# main.net
KiCad netlist of a schematic drawn in EAGLE
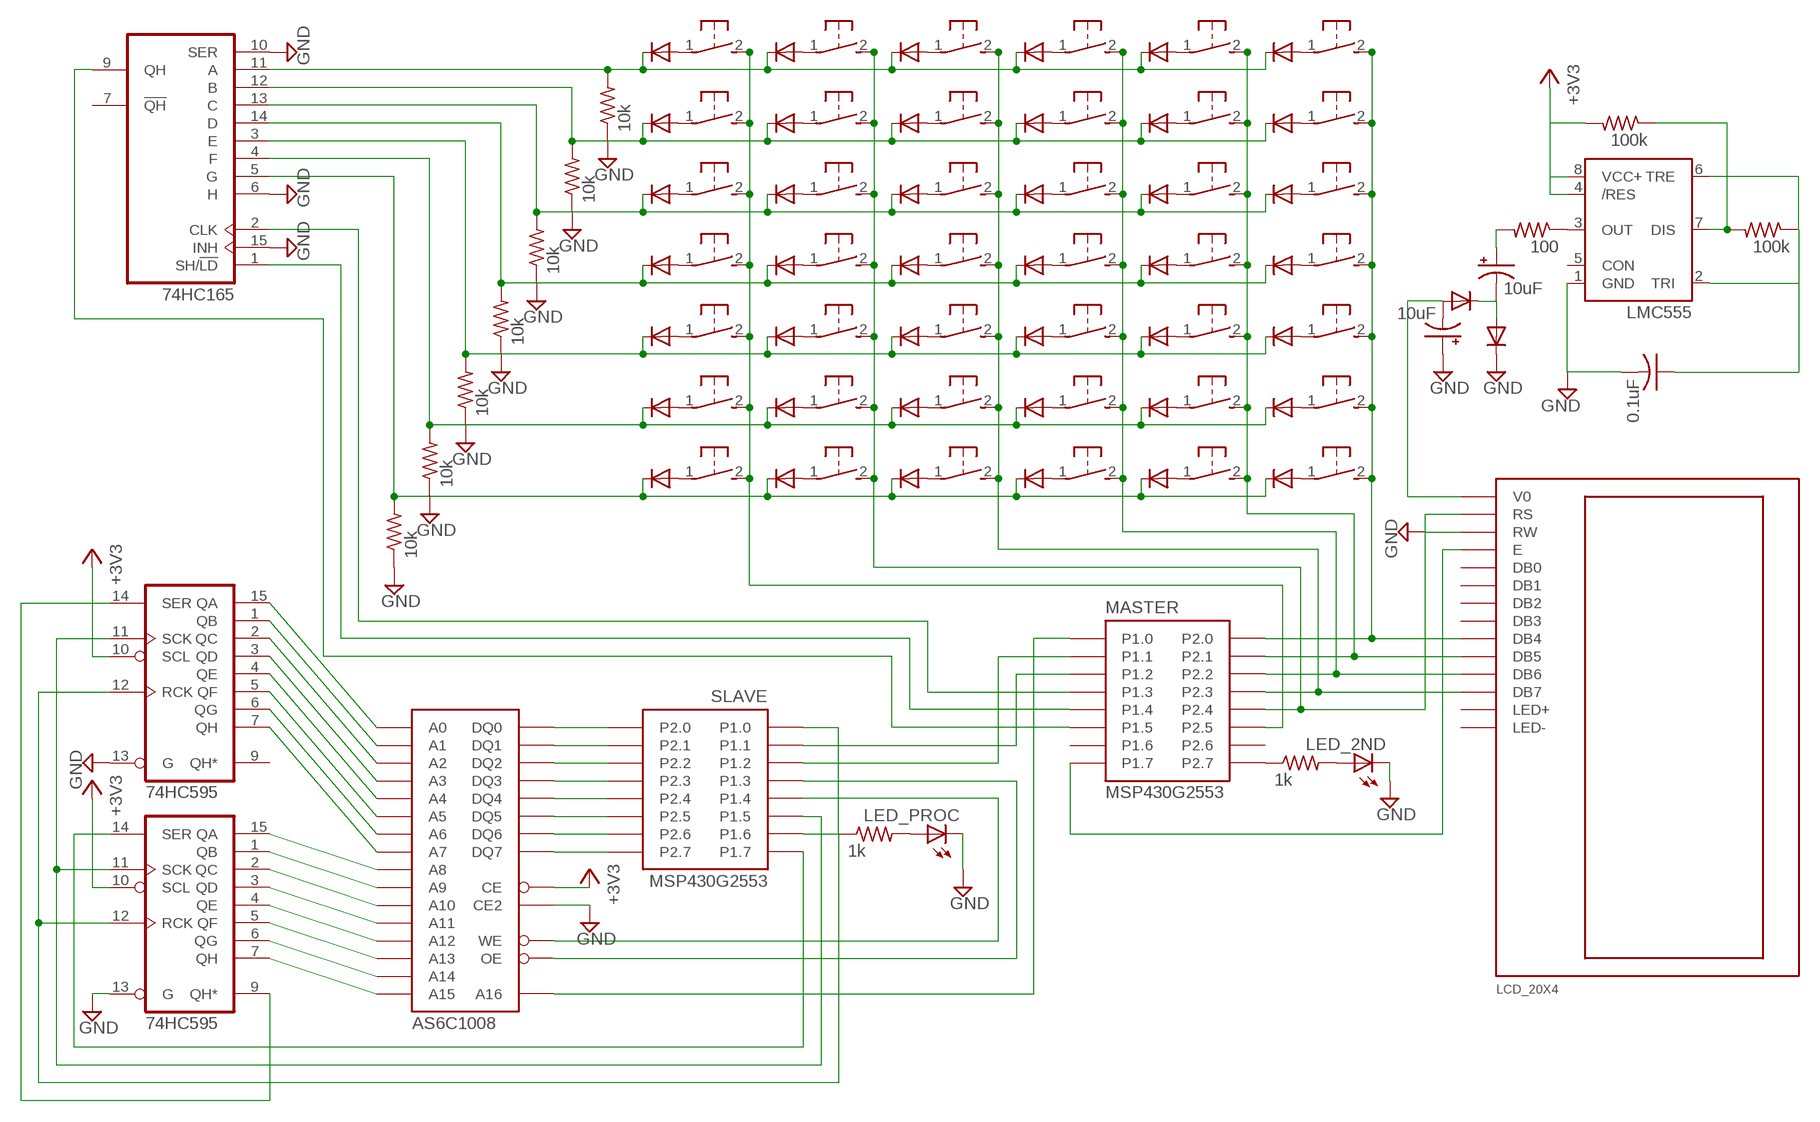
[diagram p0: schematic, sheet 1]

(export (version "E")
  (design (tool "Eeschema 10.0.6"))
  (components
    (comp (ref "C2")
      (value "0.1uF")
      (footprint "eagle-import:C025-024X044")
      (libsource (lib "eagle-import") (part "C-US025-024X044"))
    )
    (comp (ref "C4")
      (value "10uF")
      (footprint "eagle-import:085CS_1AW")
      (libsource (lib "eagle-import") (part "CPOL-US085CS-1AW"))
    )
    (comp (ref "C5")
      (value "10uF")
      (footprint "eagle-import:085CS_1AW")
      (libsource (lib "eagle-import") (part "CPOL-US085CS-1AW"))
    )
    (comp (ref "D1")
      (value "1N4148DO35-7")
      (footprint "eagle-import:DO35-7")
      (libsource (lib "eagle-import") (part "1N4148DO35-7"))
    )
    (comp (ref "D2")
      (value "1N4148DO35-7")
      (footprint "eagle-import:DO35-7")
      (libsource (lib "eagle-import") (part "1N4148DO35-7"))
    )
    (comp (ref "D3")
      (value "1N4148DO35-7")
      (footprint "eagle-import:DO35-7")
      (libsource (lib "eagle-import") (part "1N4148DO35-7"))
    )
    (comp (ref "D4")
      (value "1N4148DO35-7")
      (footprint "eagle-import:DO35-7")
      (libsource (lib "eagle-import") (part "1N4148DO35-7"))
    )
    (comp (ref "D5")
      (value "1N4148DO35-7")
      (footprint "eagle-import:DO35-7")
      (libsource (lib "eagle-import") (part "1N4148DO35-7"))
    )
    (comp (ref "D6")
      (value "1N4148DO35-7")
      (footprint "eagle-import:DO35-7")
      (libsource (lib "eagle-import") (part "1N4148DO35-7"))
    )
    (comp (ref "D7")
      (value "1N4148DO35-7")
      (footprint "eagle-import:DO35-7")
      (libsource (lib "eagle-import") (part "1N4148DO35-7"))
    )
    (comp (ref "D8")
      (value "1N4148DO35-7")
      (footprint "eagle-import:DO35-7")
      (libsource (lib "eagle-import") (part "1N4148DO35-7"))
    )
    (comp (ref "D9")
      (value "1N4148DO35-7")
      (footprint "eagle-import:DO35-7")
      (libsource (lib "eagle-import") (part "1N4148DO35-7"))
    )
    (comp (ref "D10")
      (value "1N4148DO35-7")
      (footprint "eagle-import:DO35-7")
      (libsource (lib "eagle-import") (part "1N4148DO35-7"))
    )
    (comp (ref "D11")
      (value "1N4148DO35-7")
      (footprint "eagle-import:DO35-7")
      (libsource (lib "eagle-import") (part "1N4148DO35-7"))
    )
    (comp (ref "D12")
      (value "1N4148DO35-7")
      (footprint "eagle-import:DO35-7")
      (libsource (lib "eagle-import") (part "1N4148DO35-7"))
    )
    (comp (ref "D13")
      (value "1N4148DO35-7")
      (footprint "eagle-import:DO35-7")
      (libsource (lib "eagle-import") (part "1N4148DO35-7"))
    )
    (comp (ref "D14")
      (value "1N4148DO35-7")
      (footprint "eagle-import:DO35-7")
      (libsource (lib "eagle-import") (part "1N4148DO35-7"))
    )
    (comp (ref "D15")
      (value "1N4148DO35-7")
      (footprint "eagle-import:DO35-7")
      (libsource (lib "eagle-import") (part "1N4148DO35-7"))
    )
    (comp (ref "D16")
      (value "1N4148DO35-7")
      (footprint "eagle-import:DO35-7")
      (libsource (lib "eagle-import") (part "1N4148DO35-7"))
    )
    (comp (ref "D17")
      (value "1N4148DO35-7")
      (footprint "eagle-import:DO35-7")
      (libsource (lib "eagle-import") (part "1N4148DO35-7"))
    )
    (comp (ref "D18")
      (value "1N4148DO35-7")
      (footprint "eagle-import:DO35-7")
      (libsource (lib "eagle-import") (part "1N4148DO35-7"))
    )
    (comp (ref "D19")
      (value "1N4148DO35-7")
      (footprint "eagle-import:DO35-7")
      (libsource (lib "eagle-import") (part "1N4148DO35-7"))
    )
    (comp (ref "D20")
      (value "1N4148DO35-7")
      (footprint "eagle-import:DO35-7")
      (libsource (lib "eagle-import") (part "1N4148DO35-7"))
    )
    (comp (ref "D21")
      (value "1N4148DO35-7")
      (footprint "eagle-import:DO35-7")
      (libsource (lib "eagle-import") (part "1N4148DO35-7"))
    )
    (comp (ref "D22")
      (value "1N4148DO35-7")
      (footprint "eagle-import:DO35-7")
      (libsource (lib "eagle-import") (part "1N4148DO35-7"))
    )
    (comp (ref "D23")
      (value "1N4148DO35-7")
      (footprint "eagle-import:DO35-7")
      (libsource (lib "eagle-import") (part "1N4148DO35-7"))
    )
    (comp (ref "D24")
      (value "1N4148DO35-7")
      (footprint "eagle-import:DO35-7")
      (libsource (lib "eagle-import") (part "1N4148DO35-7"))
    )
    (comp (ref "D25")
      (value "1N4148DO35-7")
      (footprint "eagle-import:DO35-7")
      (libsource (lib "eagle-import") (part "1N4148DO35-7"))
    )
    (comp (ref "D26")
      (value "1N4148DO35-7")
      (footprint "eagle-import:DO35-7")
      (libsource (lib "eagle-import") (part "1N4148DO35-7"))
    )
    (comp (ref "D27")
      (value "1N4148DO35-7")
      (footprint "eagle-import:DO35-7")
      (libsource (lib "eagle-import") (part "1N4148DO35-7"))
    )
    (comp (ref "D28")
      (value "1N4148DO35-7")
      (footprint "eagle-import:DO35-7")
      (libsource (lib "eagle-import") (part "1N4148DO35-7"))
    )
    (comp (ref "D29")
      (value "1N4148DO35-7")
      (footprint "eagle-import:DO35-7")
      (libsource (lib "eagle-import") (part "1N4148DO35-7"))
    )
    (comp (ref "D30")
      (value "1N4148DO35-7")
      (footprint "eagle-import:DO35-7")
      (libsource (lib "eagle-import") (part "1N4148DO35-7"))
    )
    (comp (ref "D31")
      (value "1N4148DO35-7")
      (footprint "eagle-import:DO35-7")
      (libsource (lib "eagle-import") (part "1N4148DO35-7"))
    )
    (comp (ref "D32")
      (value "1N4148DO35-7")
      (footprint "eagle-import:DO35-7")
      (libsource (lib "eagle-import") (part "1N4148DO35-7"))
    )
    (comp (ref "D33")
      (value "1N4148DO35-7")
      (footprint "eagle-import:DO35-7")
      (libsource (lib "eagle-import") (part "1N4148DO35-7"))
    )
    (comp (ref "D34")
      (value "1N4148DO35-7")
      (footprint "eagle-import:DO35-7")
      (libsource (lib "eagle-import") (part "1N4148DO35-7"))
    )
    (comp (ref "D35")
      (value "1N4148DO35-7")
      (footprint "eagle-import:DO35-7")
      (libsource (lib "eagle-import") (part "1N4148DO35-7"))
    )
    (comp (ref "D36")
      (value "1N4148DO35-7")
      (footprint "eagle-import:DO35-7")
      (libsource (lib "eagle-import") (part "1N4148DO35-7"))
    )
    (comp (ref "D37")
      (value "1N4148DO35-7")
      (footprint "eagle-import:DO35-7")
      (libsource (lib "eagle-import") (part "1N4148DO35-7"))
    )
    (comp (ref "D38")
      (value "1N4148DO35-7")
      (footprint "eagle-import:DO35-7")
      (libsource (lib "eagle-import") (part "1N4148DO35-7"))
    )
    (comp (ref "D39")
      (value "1N4148DO35-7")
      (footprint "eagle-import:DO35-7")
      (libsource (lib "eagle-import") (part "1N4148DO35-7"))
    )
    (comp (ref "D40")
      (value "1N4148DO35-7")
      (footprint "eagle-import:DO35-7")
      (libsource (lib "eagle-import") (part "1N4148DO35-7"))
    )
    (comp (ref "D41")
      (value "1N4148DO35-7")
      (footprint "eagle-import:DO35-7")
      (libsource (lib "eagle-import") (part "1N4148DO35-7"))
    )
    (comp (ref "D42")
      (value "1N4148DO35-7")
      (footprint "eagle-import:DO35-7")
      (libsource (lib "eagle-import") (part "1N4148DO35-7"))
    )
    (comp (ref "D45")
      (value "1N4148DO35-7")
      (footprint "eagle-import:DO35-7")
      (libsource (lib "eagle-import") (part "1N4148DO35-7"))
    )
    (comp (ref "D46")
      (value "1N4148DO35-7")
      (footprint "eagle-import:DO35-7")
      (libsource (lib "eagle-import") (part "1N4148DO35-7"))
    )
    (comp (ref "IC1")
      (value "74HC165")
      (footprint "eagle-import:DIL16")
      (libsource (lib "eagle-import") (part "74165N"))
    )
    (comp (ref "IC2")
      (value "LMC555")
      (footprint "eagle-import:DIL-08")
      (fields (field (name "MF") "Arrow Electronics") (field (name "MPN") "NE555N"))
      (libsource (lib "eagle-import") (part "NE555"))
    )
    (comp (ref "IC3")
      (value "74HC595")
      (footprint "eagle-import:DIL16")
      (libsource (lib "eagle-import") (part "74595NLS"))
    )
    (comp (ref "IC4")
      (value "74HC595")
      (footprint "eagle-import:DIL16")
      (libsource (lib "eagle-import") (part "74595NLS"))
    )
    (comp (ref "LED_2ND")
      (value "SFH482")
      (footprint "eagle-import:SFH482")
      (libsource (lib "eagle-import") (part "SFH482"))
    )
    (comp (ref "LED_PROC")
      (value "SFH482")
      (footprint "eagle-import:SFH482")
      (libsource (lib "eagle-import") (part "SFH482"))
    )
    (comp (ref "MASTER")
      (value "MSP430G2553")
      (footprint "eagle-import:MSP430G2553")
      (libsource (lib "eagle-import") (part "MSP430G2553"))
    )
    (comp (ref "R1")
      (value "1k")
      (footprint "eagle-import:0204V")
      (libsource (lib "eagle-import") (part "R-US_0204/2V"))
    )
    (comp (ref "R2")
      (value "10k")
      (footprint "eagle-import:0204V")
      (libsource (lib "eagle-import") (part "R-US_0204/2V"))
    )
    (comp (ref "R3")
      (value "10k")
      (footprint "eagle-import:0204V")
      (libsource (lib "eagle-import") (part "R-US_0204/2V"))
    )
    (comp (ref "R4")
      (value "10k")
      (footprint "eagle-import:0204V")
      (libsource (lib "eagle-import") (part "R-US_0204/2V"))
    )
    (comp (ref "R5")
      (value "10k")
      (footprint "eagle-import:0204V")
      (libsource (lib "eagle-import") (part "R-US_0204/2V"))
    )
    (comp (ref "R6")
      (value "10k")
      (footprint "eagle-import:0204V")
      (libsource (lib "eagle-import") (part "R-US_0204/2V"))
    )
    (comp (ref "R7")
      (value "10k")
      (footprint "eagle-import:0204V")
      (libsource (lib "eagle-import") (part "R-US_0204/2V"))
    )
    (comp (ref "R8")
      (value "10k")
      (footprint "eagle-import:0204V")
      (libsource (lib "eagle-import") (part "R-US_0204/2V"))
    )
    (comp (ref "R9")
      (value "100k")
      (footprint "eagle-import:0204V")
      (libsource (lib "eagle-import") (part "R-US_0204/2V"))
    )
    (comp (ref "R10")
      (value "100k")
      (footprint "eagle-import:0204V")
      (libsource (lib "eagle-import") (part "R-US_0204/2V"))
    )
    (comp (ref "R11")
      (value "100")
      (footprint "eagle-import:0204V")
      (libsource (lib "eagle-import") (part "R-US_0204/2V"))
    )
    (comp (ref "R12")
      (value "1k")
      (footprint "eagle-import:0204V")
      (libsource (lib "eagle-import") (part "R-US_0204/2V"))
    )
    (comp (ref "S1")
      (value "31-XX")
      (footprint "eagle-import:B3F-31XX")
      (fields (field (name "MPN") "B3F-3100"))
      (libsource (lib "eagle-import") (part "31-XX"))
    )
    (comp (ref "S2")
      (value "31-XX")
      (footprint "eagle-import:B3F-31XX")
      (fields (field (name "MPN") "B3F-3100"))
      (libsource (lib "eagle-import") (part "31-XX"))
    )
    (comp (ref "S3")
      (value "31-XX")
      (footprint "eagle-import:B3F-31XX")
      (fields (field (name "MPN") "B3F-3100"))
      (libsource (lib "eagle-import") (part "31-XX"))
    )
    (comp (ref "S4")
      (value "31-XX")
      (footprint "eagle-import:B3F-31XX")
      (fields (field (name "MPN") "B3F-3100"))
      (libsource (lib "eagle-import") (part "31-XX"))
    )
    (comp (ref "S5")
      (value "31-XX")
      (footprint "eagle-import:B3F-31XX")
      (fields (field (name "MPN") "B3F-3100"))
      (libsource (lib "eagle-import") (part "31-XX"))
    )
    (comp (ref "S6")
      (value "31-XX")
      (footprint "eagle-import:B3F-31XX")
      (fields (field (name "MPN") "B3F-3100"))
      (libsource (lib "eagle-import") (part "31-XX"))
    )
    (comp (ref "S7")
      (value "31-XX")
      (footprint "eagle-import:B3F-31XX")
      (fields (field (name "MPN") "B3F-3100"))
      (libsource (lib "eagle-import") (part "31-XX"))
    )
    (comp (ref "S8")
      (value "31-XX")
      (footprint "eagle-import:B3F-31XX")
      (fields (field (name "MPN") "B3F-3100"))
      (libsource (lib "eagle-import") (part "31-XX"))
    )
    (comp (ref "S9")
      (value "31-XX")
      (footprint "eagle-import:B3F-31XX")
      (fields (field (name "MPN") "B3F-3100"))
      (libsource (lib "eagle-import") (part "31-XX"))
    )
    (comp (ref "S10")
      (value "31-XX")
      (footprint "eagle-import:B3F-31XX")
      (fields (field (name "MPN") "B3F-3100"))
      (libsource (lib "eagle-import") (part "31-XX"))
    )
    (comp (ref "S11")
      (value "31-XX")
      (footprint "eagle-import:B3F-31XX")
      (fields (field (name "MPN") "B3F-3100"))
      (libsource (lib "eagle-import") (part "31-XX"))
    )
    (comp (ref "S12")
      (value "31-XX")
      (footprint "eagle-import:B3F-31XX")
      (fields (field (name "MPN") "B3F-3100"))
      (libsource (lib "eagle-import") (part "31-XX"))
    )
    (comp (ref "S13")
      (value "31-XX")
      (footprint "eagle-import:B3F-31XX")
      (fields (field (name "MPN") "B3F-3100"))
      (libsource (lib "eagle-import") (part "31-XX"))
    )
    (comp (ref "S14")
      (value "31-XX")
      (footprint "eagle-import:B3F-31XX")
      (fields (field (name "MPN") "B3F-3100"))
      (libsource (lib "eagle-import") (part "31-XX"))
    )
    (comp (ref "S15")
      (value "31-XX")
      (footprint "eagle-import:B3F-31XX")
      (fields (field (name "MPN") "B3F-3100"))
      (libsource (lib "eagle-import") (part "31-XX"))
    )
    (comp (ref "S16")
      (value "31-XX")
      (footprint "eagle-import:B3F-31XX")
      (fields (field (name "MPN") "B3F-3100"))
      (libsource (lib "eagle-import") (part "31-XX"))
    )
    (comp (ref "S17")
      (value "31-XX")
      (footprint "eagle-import:B3F-31XX")
      (fields (field (name "MPN") "B3F-3100"))
      (libsource (lib "eagle-import") (part "31-XX"))
    )
    (comp (ref "S18")
      (value "31-XX")
      (footprint "eagle-import:B3F-31XX")
      (fields (field (name "MPN") "B3F-3100"))
      (libsource (lib "eagle-import") (part "31-XX"))
    )
    (comp (ref "S19")
      (value "31-XX")
      (footprint "eagle-import:B3F-31XX")
      (fields (field (name "MPN") "B3F-3100"))
      (libsource (lib "eagle-import") (part "31-XX"))
    )
    (comp (ref "S20")
      (value "31-XX")
      (footprint "eagle-import:B3F-31XX")
      (fields (field (name "MPN") "B3F-3100"))
      (libsource (lib "eagle-import") (part "31-XX"))
    )
    (comp (ref "S21")
      (value "31-XX")
      (footprint "eagle-import:B3F-31XX")
      (fields (field (name "MPN") "B3F-3100"))
      (libsource (lib "eagle-import") (part "31-XX"))
    )
    (comp (ref "S22")
      (value "31-XX")
      (footprint "eagle-import:B3F-31XX")
      (fields (field (name "MPN") "B3F-3100"))
      (libsource (lib "eagle-import") (part "31-XX"))
    )
    (comp (ref "S23")
      (value "31-XX")
      (footprint "eagle-import:B3F-31XX")
      (fields (field (name "MPN") "B3F-3100"))
      (libsource (lib "eagle-import") (part "31-XX"))
    )
    (comp (ref "S24")
      (value "31-XX")
      (footprint "eagle-import:B3F-31XX")
      (fields (field (name "MPN") "B3F-3100"))
      (libsource (lib "eagle-import") (part "31-XX"))
    )
    (comp (ref "S25")
      (value "31-XX")
      (footprint "eagle-import:B3F-31XX")
      (fields (field (name "MPN") "B3F-3100"))
      (libsource (lib "eagle-import") (part "31-XX"))
    )
    (comp (ref "S26")
      (value "31-XX")
      (footprint "eagle-import:B3F-31XX")
      (fields (field (name "MPN") "B3F-3100"))
      (libsource (lib "eagle-import") (part "31-XX"))
    )
    (comp (ref "S27")
      (value "31-XX")
      (footprint "eagle-import:B3F-31XX")
      (fields (field (name "MPN") "B3F-3100"))
      (libsource (lib "eagle-import") (part "31-XX"))
    )
    (comp (ref "S28")
      (value "31-XX")
      (footprint "eagle-import:B3F-31XX")
      (fields (field (name "MPN") "B3F-3100"))
      (libsource (lib "eagle-import") (part "31-XX"))
    )
    (comp (ref "S29")
      (value "31-XX")
      (footprint "eagle-import:B3F-31XX")
      (fields (field (name "MPN") "B3F-3100"))
      (libsource (lib "eagle-import") (part "31-XX"))
    )
    (comp (ref "S30")
      (value "31-XX")
      (footprint "eagle-import:B3F-31XX")
      (fields (field (name "MPN") "B3F-3100"))
      (libsource (lib "eagle-import") (part "31-XX"))
    )
    (comp (ref "S31")
      (value "31-XX")
      (footprint "eagle-import:B3F-31XX")
      (fields (field (name "MPN") "B3F-3100"))
      (libsource (lib "eagle-import") (part "31-XX"))
    )
    (comp (ref "S32")
      (value "31-XX")
      (footprint "eagle-import:B3F-31XX")
      (fields (field (name "MPN") "B3F-3100"))
      (libsource (lib "eagle-import") (part "31-XX"))
    )
    (comp (ref "S33")
      (value "31-XX")
      (footprint "eagle-import:B3F-31XX")
      (fields (field (name "MPN") "B3F-3100"))
      (libsource (lib "eagle-import") (part "31-XX"))
    )
    (comp (ref "S34")
      (value "31-XX")
      (footprint "eagle-import:B3F-31XX")
      (fields (field (name "MPN") "B3F-3100"))
      (libsource (lib "eagle-import") (part "31-XX"))
    )
    (comp (ref "S35")
      (value "31-XX")
      (footprint "eagle-import:B3F-31XX")
      (fields (field (name "MPN") "B3F-3100"))
      (libsource (lib "eagle-import") (part "31-XX"))
    )
    (comp (ref "S36")
      (value "31-XX")
      (footprint "eagle-import:B3F-31XX")
      (fields (field (name "MPN") "B3F-3100"))
      (libsource (lib "eagle-import") (part "31-XX"))
    )
    (comp (ref "S37")
      (value "31-XX")
      (footprint "eagle-import:B3F-31XX")
      (fields (field (name "MPN") "B3F-3100"))
      (libsource (lib "eagle-import") (part "31-XX"))
    )
    (comp (ref "S38")
      (value "31-XX")
      (footprint "eagle-import:B3F-31XX")
      (fields (field (name "MPN") "B3F-3100"))
      (libsource (lib "eagle-import") (part "31-XX"))
    )
    (comp (ref "S39")
      (value "31-XX")
      (footprint "eagle-import:B3F-31XX")
      (fields (field (name "MPN") "B3F-3100"))
      (libsource (lib "eagle-import") (part "31-XX"))
    )
    (comp (ref "S40")
      (value "31-XX")
      (footprint "eagle-import:B3F-31XX")
      (fields (field (name "MPN") "B3F-3100"))
      (libsource (lib "eagle-import") (part "31-XX"))
    )
    (comp (ref "S41")
      (value "31-XX")
      (footprint "eagle-import:B3F-31XX")
      (fields (field (name "MPN") "B3F-3100"))
      (libsource (lib "eagle-import") (part "31-XX"))
    )
    (comp (ref "S42")
      (value "31-XX")
      (footprint "eagle-import:B3F-31XX")
      (fields (field (name "MPN") "B3F-3100"))
      (libsource (lib "eagle-import") (part "31-XX"))
    )
    (comp (ref "SLAVE")
      (value "MSP430G2553")
      (footprint "eagle-import:MSP430G2553")
      (libsource (lib "eagle-import") (part "MSP430G2553"))
    )
    (comp (ref "U$1")
      (value "LCD_20X4")
      (footprint "eagle-import:LCD_20X4")
      (libsource (lib "eagle-import") (part "LCD_20X4"))
    )
    (comp (ref "U$2")
      (value "AS6C1008")
      (footprint "eagle-import:AS6C1008")
      (libsource (lib "eagle-import") (part "AS6C1008"))
    )
  )
  (nets
    (net (code "1") (name "+3V3") (class "Default")
      (node (ref "IC2") (pin "4") (pinfunction "/RES_4") (pintype "input"))
      (node (ref "IC2") (pin "8") (pinfunction "VCC+_8") (pintype "power_in"))
      (node (ref "IC3") (pin "10") (pinfunction "SCL_10") (pintype "input"))
      (node (ref "IC4") (pin "10") (pinfunction "SCL_10") (pintype "input"))
      (node (ref "R10") (pin "2") (pinfunction "2_2") (pintype "passive"))
      (node (ref "U$2") (pin "P$18") (pinfunction "CE_P$18") (pintype "bidirectional"))
    )
    (net (code "2") (name "GND") (class "Default")
      (node (ref "C2") (pin "2") (pinfunction "2_2") (pintype "passive"))
      (node (ref "C5") (pin "+") (pinfunction "+_+") (pintype "passive"))
      (node (ref "D45") (pin "C") (pinfunction "C_C") (pintype "passive"))
      (node (ref "IC1") (pin "10") (pinfunction "SER_10") (pintype "input"))
      (node (ref "IC1") (pin "15") (pinfunction "INH_15") (pintype "input"))
      (node (ref "IC1") (pin "6") (pinfunction "H_6") (pintype "input"))
      (node (ref "IC2") (pin "1") (pinfunction "GND_1") (pintype "power_in"))
      (node (ref "IC3") (pin "13") (pinfunction "G_13") (pintype "input"))
      (node (ref "IC4") (pin "13") (pinfunction "G_13") (pintype "input"))
      (node (ref "LED_2ND") (pin "K") (pinfunction "C_K") (pintype "passive"))
      (node (ref "LED_PROC") (pin "K") (pinfunction "C_K") (pintype "passive"))
      (node (ref "R2") (pin "1") (pinfunction "1_1") (pintype "passive"))
      (node (ref "R3") (pin "1") (pinfunction "1_1") (pintype "passive"))
      (node (ref "R4") (pin "1") (pinfunction "1_1") (pintype "passive"))
      (node (ref "R5") (pin "1") (pinfunction "1_1") (pintype "passive"))
      (node (ref "R6") (pin "1") (pinfunction "1_1") (pintype "passive"))
      (node (ref "R7") (pin "1") (pinfunction "1_1") (pintype "passive"))
      (node (ref "R8") (pin "1") (pinfunction "1_1") (pintype "passive"))
      (node (ref "U$1") (pin "P$15") (pinfunction "RW_P$15") (pintype "bidirectional"))
      (node (ref "U$2") (pin "P$19") (pinfunction "CE2_P$19") (pintype "bidirectional"))
    )
    (net (code "3") (name "Net-(C4-Pad+)") (class "Default")
      (node (ref "C4") (pin "+") (pinfunction "+_+") (pintype "passive"))
      (node (ref "R11") (pin "2") (pinfunction "2_2") (pintype "passive"))
    )
    (net (code "4") (name "Net-(C4-Pad-)") (class "Default")
      (node (ref "C4") (pin "-") (pinfunction "-_-") (pintype "passive"))
      (node (ref "D45") (pin "A") (pinfunction "A_A") (pintype "passive"))
      (node (ref "D46") (pin "C") (pinfunction "C_C") (pintype "passive"))
    )
    (net (code "5") (name "Net-(IC1A-A)") (class "Default")
      (node (ref "D2") (pin "C") (pinfunction "C_C") (pintype "passive"))
      (node (ref "D4") (pin "C") (pinfunction "C_C") (pintype "passive"))
      (node (ref "D5") (pin "C") (pinfunction "C_C") (pintype "passive"))
      (node (ref "D6") (pin "C") (pinfunction "C_C") (pintype "passive"))
      (node (ref "D7") (pin "C") (pinfunction "C_C") (pintype "passive"))
      (node (ref "D8") (pin "C") (pinfunction "C_C") (pintype "passive"))
      (node (ref "IC1") (pin "11") (pinfunction "A_11") (pintype "input"))
      (node (ref "R2") (pin "2") (pinfunction "2_2") (pintype "passive"))
    )
    (net (code "6") (name "Net-(IC1A-B)") (class "Default")
      (node (ref "D1") (pin "C") (pinfunction "C_C") (pintype "passive"))
      (node (ref "D10") (pin "C") (pinfunction "C_C") (pintype "passive"))
      (node (ref "D11") (pin "C") (pinfunction "C_C") (pintype "passive"))
      (node (ref "D12") (pin "C") (pinfunction "C_C") (pintype "passive"))
      (node (ref "D3") (pin "C") (pinfunction "C_C") (pintype "passive"))
      (node (ref "D9") (pin "C") (pinfunction "C_C") (pintype "passive"))
      (node (ref "IC1") (pin "12") (pinfunction "B_12") (pintype "input"))
      (node (ref "R3") (pin "2") (pinfunction "2_2") (pintype "passive"))
    )
    (net (code "7") (name "Net-(IC1A-C)") (class "Default")
      (node (ref "D13") (pin "C") (pinfunction "C_C") (pintype "passive"))
      (node (ref "D14") (pin "C") (pinfunction "C_C") (pintype "passive"))
      (node (ref "D15") (pin "C") (pinfunction "C_C") (pintype "passive"))
      (node (ref "D16") (pin "C") (pinfunction "C_C") (pintype "passive"))
      (node (ref "D17") (pin "C") (pinfunction "C_C") (pintype "passive"))
      (node (ref "D18") (pin "C") (pinfunction "C_C") (pintype "passive"))
      (node (ref "IC1") (pin "13") (pinfunction "C_13") (pintype "input"))
      (node (ref "R4") (pin "2") (pinfunction "2_2") (pintype "passive"))
    )
    (net (code "8") (name "Net-(IC1A-CLK)") (class "Default")
      (node (ref "IC1") (pin "2") (pinfunction "CLK_2") (pintype "input"))
      (node (ref "MASTER") (pin "P$4") (pinfunction "P1.3_P$4") (pintype "bidirectional"))
    )
    (net (code "9") (name "Net-(IC1A-D)") (class "Default")
      (node (ref "D19") (pin "C") (pinfunction "C_C") (pintype "passive"))
      (node (ref "D20") (pin "C") (pinfunction "C_C") (pintype "passive"))
      (node (ref "D21") (pin "C") (pinfunction "C_C") (pintype "passive"))
      (node (ref "D22") (pin "C") (pinfunction "C_C") (pintype "passive"))
      (node (ref "D23") (pin "C") (pinfunction "C_C") (pintype "passive"))
      (node (ref "D24") (pin "C") (pinfunction "C_C") (pintype "passive"))
      (node (ref "IC1") (pin "14") (pinfunction "D_14") (pintype "input"))
      (node (ref "R5") (pin "2") (pinfunction "2_2") (pintype "passive"))
    )
    (net (code "10") (name "Net-(IC1A-E)") (class "Default")
      (node (ref "D25") (pin "C") (pinfunction "C_C") (pintype "passive"))
      (node (ref "D26") (pin "C") (pinfunction "C_C") (pintype "passive"))
      (node (ref "D27") (pin "C") (pinfunction "C_C") (pintype "passive"))
      (node (ref "D28") (pin "C") (pinfunction "C_C") (pintype "passive"))
      (node (ref "D29") (pin "C") (pinfunction "C_C") (pintype "passive"))
      (node (ref "D30") (pin "C") (pinfunction "C_C") (pintype "passive"))
      (node (ref "IC1") (pin "3") (pinfunction "E_3") (pintype "input"))
      (node (ref "R6") (pin "2") (pinfunction "2_2") (pintype "passive"))
    )
    (net (code "11") (name "Net-(IC1A-F)") (class "Default")
      (node (ref "D31") (pin "C") (pinfunction "C_C") (pintype "passive"))
      (node (ref "D32") (pin "C") (pinfunction "C_C") (pintype "passive"))
      (node (ref "D33") (pin "C") (pinfunction "C_C") (pintype "passive"))
      (node (ref "D34") (pin "C") (pinfunction "C_C") (pintype "passive"))
      (node (ref "D35") (pin "C") (pinfunction "C_C") (pintype "passive"))
      (node (ref "D36") (pin "C") (pinfunction "C_C") (pintype "passive"))
      (node (ref "IC1") (pin "4") (pinfunction "F_4") (pintype "input"))
      (node (ref "R7") (pin "2") (pinfunction "2_2") (pintype "passive"))
    )
    (net (code "12") (name "Net-(IC1A-G)") (class "Default")
      (node (ref "D37") (pin "C") (pinfunction "C_C") (pintype "passive"))
      (node (ref "D38") (pin "C") (pinfunction "C_C") (pintype "passive"))
      (node (ref "D39") (pin "C") (pinfunction "C_C") (pintype "passive"))
      (node (ref "D40") (pin "C") (pinfunction "C_C") (pintype "passive"))
      (node (ref "D41") (pin "C") (pinfunction "C_C") (pintype "passive"))
      (node (ref "D42") (pin "C") (pinfunction "C_C") (pintype "passive"))
      (node (ref "IC1") (pin "5") (pinfunction "G_5") (pintype "input"))
      (node (ref "R8") (pin "2") (pinfunction "2_2") (pintype "passive"))
    )
    (net (code "13") (name "Net-(IC1A-QH)") (class "Default")
      (node (ref "IC1") (pin "9") (pinfunction "QH_9") (pintype "output"))
      (node (ref "MASTER") (pin "P$6") (pinfunction "P1.5_P$6") (pintype "bidirectional"))
    )
    (net (code "14") (name "Net-(IC1A-SH{slash}~{LD})") (class "Default")
      (node (ref "IC1") (pin "1") (pinfunction "SH/~{LD}_1") (pintype "input"))
      (node (ref "MASTER") (pin "P$5") (pinfunction "P1.4_P$5") (pintype "bidirectional"))
    )
    (net (code "15") (name "Net-(IC2-DIS)") (class "Default")
      (node (ref "IC2") (pin "7") (pinfunction "DIS_7") (pintype "input"))
      (node (ref "R10") (pin "1") (pinfunction "1_1") (pintype "passive"))
      (node (ref "R9") (pin "2") (pinfunction "2_2") (pintype "passive"))
    )
    (net (code "16") (name "Net-(IC2-OUT)") (class "Default")
      (node (ref "IC2") (pin "3") (pinfunction "OUT_3") (pintype "output"))
      (node (ref "R11") (pin "1") (pinfunction "1_1") (pintype "passive"))
    )
    (net (code "17") (name "Net-(IC2-TRE)") (class "Default")
      (node (ref "C2") (pin "1") (pinfunction "1_1") (pintype "passive"))
      (node (ref "IC2") (pin "2") (pinfunction "TRI_2") (pintype "input"))
      (node (ref "IC2") (pin "6") (pinfunction "TRE_6") (pintype "input"))
      (node (ref "R9") (pin "1") (pinfunction "1_1") (pintype "passive"))
    )
    (net (code "18") (name "Net-(IC3A-QA)") (class "Default")
      (node (ref "IC3") (pin "15") (pinfunction "QA_15") (pintype "tri_state"))
      (node (ref "U$2") (pin "P$1") (pinfunction "A0_P$1") (pintype "bidirectional"))
    )
    (net (code "19") (name "Net-(IC3A-QB)") (class "Default")
      (node (ref "IC3") (pin "1") (pinfunction "QB_1") (pintype "tri_state"))
      (node (ref "U$2") (pin "P$2") (pinfunction "A1_P$2") (pintype "bidirectional"))
    )
    (net (code "20") (name "Net-(IC3A-QC)") (class "Default")
      (node (ref "IC3") (pin "2") (pinfunction "QC_2") (pintype "tri_state"))
      (node (ref "U$2") (pin "P$3") (pinfunction "A2_P$3") (pintype "bidirectional"))
    )
    (net (code "21") (name "Net-(IC3A-QD)") (class "Default")
      (node (ref "IC3") (pin "3") (pinfunction "QD_3") (pintype "tri_state"))
      (node (ref "U$2") (pin "P$4") (pinfunction "A3_P$4") (pintype "bidirectional"))
    )
    (net (code "22") (name "Net-(IC3A-QE)") (class "Default")
      (node (ref "IC3") (pin "4") (pinfunction "QE_4") (pintype "tri_state"))
      (node (ref "U$2") (pin "P$5") (pinfunction "A4_P$5") (pintype "bidirectional"))
    )
    (net (code "23") (name "Net-(IC3A-QF)") (class "Default")
      (node (ref "IC3") (pin "5") (pinfunction "QF_5") (pintype "tri_state"))
      (node (ref "U$2") (pin "P$6") (pinfunction "A5_P$6") (pintype "bidirectional"))
    )
    (net (code "24") (name "Net-(IC3A-QG)") (class "Default")
      (node (ref "IC3") (pin "6") (pinfunction "QG_6") (pintype "tri_state"))
      (node (ref "U$2") (pin "P$7") (pinfunction "A6_P$7") (pintype "bidirectional"))
    )
    (net (code "25") (name "Net-(IC3A-QH)") (class "Default")
      (node (ref "IC3") (pin "7") (pinfunction "QH_7") (pintype "tri_state"))
      (node (ref "U$2") (pin "P$8") (pinfunction "A7_P$8") (pintype "bidirectional"))
    )
    (net (code "26") (name "Net-(IC3A-RCK)") (class "Default")
      (node (ref "IC3") (pin "12") (pinfunction "RCK_12") (pintype "input"))
      (node (ref "IC4") (pin "12") (pinfunction "RCK_12") (pintype "input"))
      (node (ref "R12") (pin "1") (pinfunction "1_1") (pintype "passive"))
      (node (ref "SLAVE") (pin "P$1") (pinfunction "P1.0_P$1") (pintype "bidirectional"))
      (node (ref "SLAVE") (pin "P$7") (pinfunction "P1.6_P$7") (pintype "bidirectional"))
    )
    (net (code "27") (name "Net-(IC3A-SCK)") (class "Default")
      (node (ref "IC3") (pin "11") (pinfunction "SCK_11") (pintype "input"))
      (node (ref "IC4") (pin "11") (pinfunction "SCK_11") (pintype "input"))
      (node (ref "SLAVE") (pin "P$6") (pinfunction "P1.5_P$6") (pintype "bidirectional"))
    )
    (net (code "28") (name "Net-(IC3A-SER)") (class "Default")
      (node (ref "IC3") (pin "14") (pinfunction "SER_14") (pintype "input"))
      (node (ref "IC4") (pin "9") (pinfunction "QH*_9") (pintype "tri_state"))
    )
    (net (code "29") (name "Net-(IC4A-QA)") (class "Default")
      (node (ref "IC4") (pin "15") (pinfunction "QA_15") (pintype "tri_state"))
      (node (ref "U$2") (pin "P$9") (pinfunction "A8_P$9") (pintype "bidirectional"))
    )
    (net (code "30") (name "Net-(IC4A-QB)") (class "Default")
      (node (ref "IC4") (pin "1") (pinfunction "QB_1") (pintype "tri_state"))
      (node (ref "U$2") (pin "P$10") (pinfunction "A9_P$10") (pintype "bidirectional"))
    )
    (net (code "31") (name "Net-(IC4A-QC)") (class "Default")
      (node (ref "IC4") (pin "2") (pinfunction "QC_2") (pintype "tri_state"))
      (node (ref "U$2") (pin "P$11") (pinfunction "A10_P$11") (pintype "bidirectional"))
    )
    (net (code "32") (name "Net-(IC4A-QD)") (class "Default")
      (node (ref "IC4") (pin "3") (pinfunction "QD_3") (pintype "tri_state"))
      (node (ref "U$2") (pin "P$12") (pinfunction "A11_P$12") (pintype "bidirectional"))
    )
    (net (code "33") (name "Net-(IC4A-QE)") (class "Default")
      (node (ref "IC4") (pin "4") (pinfunction "QE_4") (pintype "tri_state"))
      (node (ref "U$2") (pin "P$13") (pinfunction "A12_P$13") (pintype "bidirectional"))
    )
    (net (code "34") (name "Net-(IC4A-QF)") (class "Default")
      (node (ref "IC4") (pin "5") (pinfunction "QF_5") (pintype "tri_state"))
      (node (ref "U$2") (pin "P$14") (pinfunction "A13_P$14") (pintype "bidirectional"))
    )
    (net (code "35") (name "Net-(IC4A-QG)") (class "Default")
      (node (ref "IC4") (pin "6") (pinfunction "QG_6") (pintype "tri_state"))
      (node (ref "U$2") (pin "P$15") (pinfunction "A14_P$15") (pintype "bidirectional"))
    )
    (net (code "36") (name "Net-(IC4A-QH)") (class "Default")
      (node (ref "IC4") (pin "7") (pinfunction "QH_7") (pintype "tri_state"))
      (node (ref "U$2") (pin "P$16") (pinfunction "A15_P$16") (pintype "bidirectional"))
    )
    (net (code "37") (name "Net-(IC4A-SER)") (class "Default")
      (node (ref "IC4") (pin "14") (pinfunction "SER_14") (pintype "input"))
      (node (ref "SLAVE") (pin "P$8") (pinfunction "P1.7_P$8") (pintype "bidirectional"))
    )
    (net (code "38") (name "Net-(LED_2ND-PadA)") (class "Default")
      (node (ref "LED_2ND") (pin "A") (pinfunction "A_A") (pintype "passive"))
      (node (ref "R1") (pin "2") (pinfunction "2_2") (pintype "passive"))
    )
    (net (code "39") (name "Net-(LED_PROC-PadA)") (class "Default")
      (node (ref "LED_PROC") (pin "A") (pinfunction "A_A") (pintype "passive"))
      (node (ref "R12") (pin "2") (pinfunction "2_2") (pintype "passive"))
    )
    (net (code "40") (name "Net-(MASTER-P1.0)") (class "Default")
      (node (ref "MASTER") (pin "P$1") (pinfunction "P1.0_P$1") (pintype "bidirectional"))
      (node (ref "U$2") (pin "P$17") (pinfunction "A16_P$17") (pintype "bidirectional"))
    )
    (net (code "41") (name "Net-(MASTER-P1.1)") (class "Default")
      (node (ref "MASTER") (pin "P$2") (pinfunction "P1.1_P$2") (pintype "bidirectional"))
      (node (ref "SLAVE") (pin "P$3") (pinfunction "P1.2_P$3") (pintype "bidirectional"))
    )
    (net (code "42") (name "Net-(MASTER-P1.2)") (class "Default")
      (node (ref "MASTER") (pin "P$3") (pinfunction "P1.2_P$3") (pintype "bidirectional"))
      (node (ref "SLAVE") (pin "P$2") (pinfunction "P1.1_P$2") (pintype "bidirectional"))
    )
    (net (code "43") (name "Net-(MASTER-P1.7)") (class "Default")
      (node (ref "MASTER") (pin "P$8") (pinfunction "P1.7_P$8") (pintype "bidirectional"))
      (node (ref "U$1") (pin "P$11") (pinfunction "E_P$11") (pintype "bidirectional"))
    )
    (net (code "44") (name "Net-(MASTER-P2.0)") (class "Default")
      (node (ref "MASTER") (pin "P$9") (pinfunction "P2.0_P$9") (pintype "bidirectional"))
      (node (ref "S12") (pin "2") (pinfunction "S_2") (pintype "passive"))
      (node (ref "S18") (pin "2") (pinfunction "S_2") (pintype "passive"))
      (node (ref "S24") (pin "2") (pinfunction "S_2") (pintype "passive"))
      (node (ref "S30") (pin "2") (pinfunction "S_2") (pintype "passive"))
      (node (ref "S36") (pin "2") (pinfunction "S_2") (pintype "passive"))
      (node (ref "S38") (pin "2") (pinfunction "S_2") (pintype "passive"))
      (node (ref "S6") (pin "2") (pinfunction "S_2") (pintype "passive"))
      (node (ref "U$1") (pin "P$5") (pinfunction "DB4_P$5") (pintype "bidirectional"))
    )
    (net (code "45") (name "Net-(MASTER-P2.1)") (class "Default")
      (node (ref "MASTER") (pin "P$10") (pinfunction "P2.1_P$10") (pintype "bidirectional"))
      (node (ref "S11") (pin "2") (pinfunction "S_2") (pintype "passive"))
      (node (ref "S17") (pin "2") (pinfunction "S_2") (pintype "passive"))
      (node (ref "S23") (pin "2") (pinfunction "S_2") (pintype "passive"))
      (node (ref "S29") (pin "2") (pinfunction "S_2") (pintype "passive"))
      (node (ref "S35") (pin "2") (pinfunction "S_2") (pintype "passive"))
      (node (ref "S37") (pin "2") (pinfunction "S_2") (pintype "passive"))
      (node (ref "S5") (pin "2") (pinfunction "S_2") (pintype "passive"))
      (node (ref "U$1") (pin "P$6") (pinfunction "DB5_P$6") (pintype "bidirectional"))
    )
    (net (code "46") (name "Net-(MASTER-P2.2)") (class "Default")
      (node (ref "MASTER") (pin "P$11") (pinfunction "P2.2_P$11") (pintype "bidirectional"))
      (node (ref "S1") (pin "2") (pinfunction "S_2") (pintype "passive"))
      (node (ref "S13") (pin "2") (pinfunction "S_2") (pintype "passive"))
      (node (ref "S19") (pin "2") (pinfunction "S_2") (pintype "passive"))
      (node (ref "S25") (pin "2") (pinfunction "S_2") (pintype "passive"))
      (node (ref "S31") (pin "2") (pinfunction "S_2") (pintype "passive"))
      (node (ref "S39") (pin "2") (pinfunction "S_2") (pintype "passive"))
      (node (ref "S7") (pin "2") (pinfunction "S_2") (pintype "passive"))
      (node (ref "U$1") (pin "P$7") (pinfunction "DB6_P$7") (pintype "bidirectional"))
    )
    (net (code "47") (name "Net-(MASTER-P2.3)") (class "Default")
      (node (ref "MASTER") (pin "P$12") (pinfunction "P2.3_P$12") (pintype "bidirectional"))
      (node (ref "S14") (pin "2") (pinfunction "S_2") (pintype "passive"))
      (node (ref "S2") (pin "2") (pinfunction "S_2") (pintype "passive"))
      (node (ref "S20") (pin "2") (pinfunction "S_2") (pintype "passive"))
      (node (ref "S26") (pin "2") (pinfunction "S_2") (pintype "passive"))
      (node (ref "S32") (pin "2") (pinfunction "S_2") (pintype "passive"))
      (node (ref "S40") (pin "2") (pinfunction "S_2") (pintype "passive"))
      (node (ref "S8") (pin "2") (pinfunction "S_2") (pintype "passive"))
      (node (ref "U$1") (pin "P$8") (pinfunction "DB7_P$8") (pintype "bidirectional"))
    )
    (net (code "48") (name "Net-(MASTER-P2.4)") (class "Default")
      (node (ref "MASTER") (pin "P$13") (pinfunction "P2.4_P$13") (pintype "bidirectional"))
      (node (ref "S15") (pin "2") (pinfunction "S_2") (pintype "passive"))
      (node (ref "S21") (pin "2") (pinfunction "S_2") (pintype "passive"))
      (node (ref "S27") (pin "2") (pinfunction "S_2") (pintype "passive"))
      (node (ref "S3") (pin "2") (pinfunction "S_2") (pintype "passive"))
      (node (ref "S33") (pin "2") (pinfunction "S_2") (pintype "passive"))
      (node (ref "S41") (pin "2") (pinfunction "S_2") (pintype "passive"))
      (node (ref "S9") (pin "2") (pinfunction "S_2") (pintype "passive"))
      (node (ref "U$1") (pin "P$14") (pinfunction "RS_P$14") (pintype "bidirectional"))
    )
    (net (code "49") (name "Net-(MASTER-P2.5)") (class "Default")
      (node (ref "MASTER") (pin "P$14") (pinfunction "P2.5_P$14") (pintype "bidirectional"))
      (node (ref "S10") (pin "2") (pinfunction "S_2") (pintype "passive"))
      (node (ref "S16") (pin "2") (pinfunction "S_2") (pintype "passive"))
      (node (ref "S22") (pin "2") (pinfunction "S_2") (pintype "passive"))
      (node (ref "S28") (pin "2") (pinfunction "S_2") (pintype "passive"))
      (node (ref "S34") (pin "2") (pinfunction "S_2") (pintype "passive"))
      (node (ref "S4") (pin "2") (pinfunction "S_2") (pintype "passive"))
      (node (ref "S42") (pin "2") (pinfunction "S_2") (pintype "passive"))
    )
    (net (code "50") (name "Net-(MASTER-P2.7)") (class "Default")
      (node (ref "MASTER") (pin "P$16") (pinfunction "P2.7_P$16") (pintype "bidirectional"))
      (node (ref "R1") (pin "1") (pinfunction "1_1") (pintype "passive"))
    )
    (net (code "51") (name "Net-(S1-P)") (class "Default")
      (node (ref "D4") (pin "A") (pinfunction "A_A") (pintype "passive"))
      (node (ref "S1") (pin "1") (pinfunction "P_1") (pintype "passive"))
    )
    (net (code "52") (name "Net-(S2-P)") (class "Default")
      (node (ref "D6") (pin "A") (pinfunction "A_A") (pintype "passive"))
      (node (ref "S2") (pin "1") (pinfunction "P_1") (pintype "passive"))
    )
    (net (code "53") (name "Net-(S3-P)") (class "Default")
      (node (ref "D7") (pin "A") (pinfunction "A_A") (pintype "passive"))
      (node (ref "S3") (pin "1") (pinfunction "P_1") (pintype "passive"))
    )
    (net (code "54") (name "Net-(S4-P)") (class "Default")
      (node (ref "D8") (pin "A") (pinfunction "A_A") (pintype "passive"))
      (node (ref "S4") (pin "1") (pinfunction "P_1") (pintype "passive"))
    )
    (net (code "55") (name "Net-(S5-P)") (class "Default")
      (node (ref "D3") (pin "A") (pinfunction "A_A") (pintype "passive"))
      (node (ref "S5") (pin "1") (pinfunction "P_1") (pintype "passive"))
    )
    (net (code "56") (name "Net-(S6-P)") (class "Default")
      (node (ref "D1") (pin "A") (pinfunction "A_A") (pintype "passive"))
      (node (ref "S6") (pin "1") (pinfunction "P_1") (pintype "passive"))
    )
    (net (code "57") (name "Net-(S7-P)") (class "Default")
      (node (ref "D9") (pin "A") (pinfunction "A_A") (pintype "passive"))
      (node (ref "S7") (pin "1") (pinfunction "P_1") (pintype "passive"))
    )
    (net (code "58") (name "Net-(S8-P)") (class "Default")
      (node (ref "D10") (pin "A") (pinfunction "A_A") (pintype "passive"))
      (node (ref "S8") (pin "1") (pinfunction "P_1") (pintype "passive"))
    )
    (net (code "59") (name "Net-(S9-P)") (class "Default")
      (node (ref "D11") (pin "A") (pinfunction "A_A") (pintype "passive"))
      (node (ref "S9") (pin "1") (pinfunction "P_1") (pintype "passive"))
    )
    (net (code "60") (name "Net-(S10-P)") (class "Default")
      (node (ref "D12") (pin "A") (pinfunction "A_A") (pintype "passive"))
      (node (ref "S10") (pin "1") (pinfunction "P_1") (pintype "passive"))
    )
    (net (code "61") (name "Net-(S11-P)") (class "Default")
      (node (ref "D14") (pin "A") (pinfunction "A_A") (pintype "passive"))
      (node (ref "S11") (pin "1") (pinfunction "P_1") (pintype "passive"))
    )
    (net (code "62") (name "Net-(S12-P)") (class "Default")
      (node (ref "D13") (pin "A") (pinfunction "A_A") (pintype "passive"))
      (node (ref "S12") (pin "1") (pinfunction "P_1") (pintype "passive"))
    )
    (net (code "63") (name "Net-(S13-P)") (class "Default")
      (node (ref "D15") (pin "A") (pinfunction "A_A") (pintype "passive"))
      (node (ref "S13") (pin "1") (pinfunction "P_1") (pintype "passive"))
    )
    (net (code "64") (name "Net-(S14-P)") (class "Default")
      (node (ref "D16") (pin "A") (pinfunction "A_A") (pintype "passive"))
      (node (ref "S14") (pin "1") (pinfunction "P_1") (pintype "passive"))
    )
    (net (code "65") (name "Net-(S15-P)") (class "Default")
      (node (ref "D17") (pin "A") (pinfunction "A_A") (pintype "passive"))
      (node (ref "S15") (pin "1") (pinfunction "P_1") (pintype "passive"))
    )
    (net (code "66") (name "Net-(S16-P)") (class "Default")
      (node (ref "D18") (pin "A") (pinfunction "A_A") (pintype "passive"))
      (node (ref "S16") (pin "1") (pinfunction "P_1") (pintype "passive"))
    )
    (net (code "67") (name "Net-(S17-P)") (class "Default")
      (node (ref "D20") (pin "A") (pinfunction "A_A") (pintype "passive"))
      (node (ref "S17") (pin "1") (pinfunction "P_1") (pintype "passive"))
    )
    (net (code "68") (name "Net-(S18-P)") (class "Default")
      (node (ref "D19") (pin "A") (pinfunction "A_A") (pintype "passive"))
      (node (ref "S18") (pin "1") (pinfunction "P_1") (pintype "passive"))
    )
    (net (code "69") (name "Net-(S19-P)") (class "Default")
      (node (ref "D21") (pin "A") (pinfunction "A_A") (pintype "passive"))
      (node (ref "S19") (pin "1") (pinfunction "P_1") (pintype "passive"))
    )
    (net (code "70") (name "Net-(S20-P)") (class "Default")
      (node (ref "D22") (pin "A") (pinfunction "A_A") (pintype "passive"))
      (node (ref "S20") (pin "1") (pinfunction "P_1") (pintype "passive"))
    )
    (net (code "71") (name "Net-(S21-P)") (class "Default")
      (node (ref "D23") (pin "A") (pinfunction "A_A") (pintype "passive"))
      (node (ref "S21") (pin "1") (pinfunction "P_1") (pintype "passive"))
    )
    (net (code "72") (name "Net-(S22-P)") (class "Default")
      (node (ref "D24") (pin "A") (pinfunction "A_A") (pintype "passive"))
      (node (ref "S22") (pin "1") (pinfunction "P_1") (pintype "passive"))
    )
    (net (code "73") (name "Net-(S23-P)") (class "Default")
      (node (ref "D26") (pin "A") (pinfunction "A_A") (pintype "passive"))
      (node (ref "S23") (pin "1") (pinfunction "P_1") (pintype "passive"))
    )
    (net (code "74") (name "Net-(S24-P)") (class "Default")
      (node (ref "D25") (pin "A") (pinfunction "A_A") (pintype "passive"))
      (node (ref "S24") (pin "1") (pinfunction "P_1") (pintype "passive"))
    )
    (net (code "75") (name "Net-(S25-P)") (class "Default")
      (node (ref "D27") (pin "A") (pinfunction "A_A") (pintype "passive"))
      (node (ref "S25") (pin "1") (pinfunction "P_1") (pintype "passive"))
    )
    (net (code "76") (name "Net-(S26-P)") (class "Default")
      (node (ref "D28") (pin "A") (pinfunction "A_A") (pintype "passive"))
      (node (ref "S26") (pin "1") (pinfunction "P_1") (pintype "passive"))
    )
    (net (code "77") (name "Net-(S27-P)") (class "Default")
      (node (ref "D29") (pin "A") (pinfunction "A_A") (pintype "passive"))
      (node (ref "S27") (pin "1") (pinfunction "P_1") (pintype "passive"))
    )
    (net (code "78") (name "Net-(S28-P)") (class "Default")
      (node (ref "D30") (pin "A") (pinfunction "A_A") (pintype "passive"))
      (node (ref "S28") (pin "1") (pinfunction "P_1") (pintype "passive"))
    )
    (net (code "79") (name "Net-(S29-P)") (class "Default")
      (node (ref "D32") (pin "A") (pinfunction "A_A") (pintype "passive"))
      (node (ref "S29") (pin "1") (pinfunction "P_1") (pintype "passive"))
    )
    (net (code "80") (name "Net-(S30-P)") (class "Default")
      (node (ref "D31") (pin "A") (pinfunction "A_A") (pintype "passive"))
      (node (ref "S30") (pin "1") (pinfunction "P_1") (pintype "passive"))
    )
    (net (code "81") (name "Net-(S31-P)") (class "Default")
      (node (ref "D33") (pin "A") (pinfunction "A_A") (pintype "passive"))
      (node (ref "S31") (pin "1") (pinfunction "P_1") (pintype "passive"))
    )
    (net (code "82") (name "Net-(S32-P)") (class "Default")
      (node (ref "D34") (pin "A") (pinfunction "A_A") (pintype "passive"))
      (node (ref "S32") (pin "1") (pinfunction "P_1") (pintype "passive"))
    )
    (net (code "83") (name "Net-(S33-P)") (class "Default")
      (node (ref "D35") (pin "A") (pinfunction "A_A") (pintype "passive"))
      (node (ref "S33") (pin "1") (pinfunction "P_1") (pintype "passive"))
    )
    (net (code "84") (name "Net-(S34-P)") (class "Default")
      (node (ref "D36") (pin "A") (pinfunction "A_A") (pintype "passive"))
      (node (ref "S34") (pin "1") (pinfunction "P_1") (pintype "passive"))
    )
    (net (code "85") (name "Net-(S35-P)") (class "Default")
      (node (ref "D38") (pin "A") (pinfunction "A_A") (pintype "passive"))
      (node (ref "S35") (pin "1") (pinfunction "P_1") (pintype "passive"))
    )
    (net (code "86") (name "Net-(S36-P)") (class "Default")
      (node (ref "D37") (pin "A") (pinfunction "A_A") (pintype "passive"))
      (node (ref "S36") (pin "1") (pinfunction "P_1") (pintype "passive"))
    )
    (net (code "87") (name "Net-(S37-P)") (class "Default")
      (node (ref "D5") (pin "A") (pinfunction "A_A") (pintype "passive"))
      (node (ref "S37") (pin "1") (pinfunction "P_1") (pintype "passive"))
    )
    (net (code "88") (name "Net-(S38-P)") (class "Default")
      (node (ref "D2") (pin "A") (pinfunction "A_A") (pintype "passive"))
      (node (ref "S38") (pin "1") (pinfunction "P_1") (pintype "passive"))
    )
    (net (code "89") (name "Net-(S39-P)") (class "Default")
      (node (ref "D39") (pin "A") (pinfunction "A_A") (pintype "passive"))
      (node (ref "S39") (pin "1") (pinfunction "P_1") (pintype "passive"))
    )
    (net (code "90") (name "Net-(S40-P)") (class "Default")
      (node (ref "D40") (pin "A") (pinfunction "A_A") (pintype "passive"))
      (node (ref "S40") (pin "1") (pinfunction "P_1") (pintype "passive"))
    )
    (net (code "91") (name "Net-(S41-P)") (class "Default")
      (node (ref "D41") (pin "A") (pinfunction "A_A") (pintype "passive"))
      (node (ref "S41") (pin "1") (pinfunction "P_1") (pintype "passive"))
    )
    (net (code "92") (name "Net-(S42-P)") (class "Default")
      (node (ref "D42") (pin "A") (pinfunction "A_A") (pintype "passive"))
      (node (ref "S42") (pin "1") (pinfunction "P_1") (pintype "passive"))
    )
    (net (code "93") (name "Net-(SLAVE-P1.3)") (class "Default")
      (node (ref "SLAVE") (pin "P$4") (pinfunction "P1.3_P$4") (pintype "bidirectional"))
      (node (ref "U$2") (pin "P$28") (pinfunction "OE_P$28") (pintype "bidirectional"))
    )
    (net (code "94") (name "Net-(SLAVE-P1.4)") (class "Default")
      (node (ref "SLAVE") (pin "P$5") (pinfunction "P1.4_P$5") (pintype "bidirectional"))
      (node (ref "U$2") (pin "P$29") (pinfunction "WE_P$29") (pintype "bidirectional"))
    )
    (net (code "95") (name "Net-(SLAVE-P2.0)") (class "Default")
      (node (ref "SLAVE") (pin "P$9") (pinfunction "P2.0_P$9") (pintype "bidirectional"))
      (node (ref "U$2") (pin "P$20") (pinfunction "DQ0_P$20") (pintype "bidirectional"))
    )
    (net (code "96") (name "Net-(SLAVE-P2.1)") (class "Default")
      (node (ref "SLAVE") (pin "P$10") (pinfunction "P2.1_P$10") (pintype "bidirectional"))
      (node (ref "U$2") (pin "P$21") (pinfunction "DQ1_P$21") (pintype "bidirectional"))
    )
    (net (code "97") (name "Net-(SLAVE-P2.2)") (class "Default")
      (node (ref "SLAVE") (pin "P$11") (pinfunction "P2.2_P$11") (pintype "bidirectional"))
      (node (ref "U$2") (pin "P$22") (pinfunction "DQ2_P$22") (pintype "bidirectional"))
    )
    (net (code "98") (name "Net-(SLAVE-P2.3)") (class "Default")
      (node (ref "SLAVE") (pin "P$12") (pinfunction "P2.3_P$12") (pintype "bidirectional"))
      (node (ref "U$2") (pin "P$23") (pinfunction "DQ3_P$23") (pintype "bidirectional"))
    )
    (net (code "99") (name "Net-(SLAVE-P2.4)") (class "Default")
      (node (ref "SLAVE") (pin "P$13") (pinfunction "P2.4_P$13") (pintype "bidirectional"))
      (node (ref "U$2") (pin "P$24") (pinfunction "DQ4_P$24") (pintype "bidirectional"))
    )
    (net (code "100") (name "Net-(SLAVE-P2.5)") (class "Default")
      (node (ref "SLAVE") (pin "P$14") (pinfunction "P2.5_P$14") (pintype "bidirectional"))
      (node (ref "U$2") (pin "P$25") (pinfunction "DQ5_P$25") (pintype "bidirectional"))
    )
    (net (code "101") (name "Net-(SLAVE-P2.6)") (class "Default")
      (node (ref "SLAVE") (pin "P$15") (pinfunction "P2.6_P$15") (pintype "bidirectional"))
      (node (ref "U$2") (pin "P$26") (pinfunction "DQ6_P$26") (pintype "bidirectional"))
    )
    (net (code "102") (name "Net-(SLAVE-P2.7)") (class "Default")
      (node (ref "SLAVE") (pin "P$16") (pinfunction "P2.7_P$16") (pintype "bidirectional"))
      (node (ref "U$2") (pin "P$27") (pinfunction "DQ7_P$27") (pintype "bidirectional"))
    )
    (net (code "103") (name "Net-(U$1-V0)") (class "Default")
      (node (ref "C5") (pin "-") (pinfunction "-_-") (pintype "passive"))
      (node (ref "D46") (pin "A") (pinfunction "A_A") (pintype "passive"))
      (node (ref "U$1") (pin "P$16") (pinfunction "V0_P$16") (pintype "bidirectional"))
    )
    (net (code "104") (name "unconnected-(IC1A-~{QH}-Pad7)") (class "Default")
      (node (ref "IC1") (pin "7") (pinfunction "~{QH}_7") (pintype "output"))
    )
    (net (code "105") (name "unconnected-(IC2-CON-Pad5)") (class "Default")
      (node (ref "IC2") (pin "5") (pinfunction "CON_5") (pintype "input"))
    )
    (net (code "106") (name "unconnected-(IC3A-QH*-Pad9)") (class "Default")
      (node (ref "IC3") (pin "9") (pinfunction "QH*_9") (pintype "tri_state"))
    )
    (net (code "107") (name "unconnected-(MASTER-P1.6-PadP$7)") (class "Default")
      (node (ref "MASTER") (pin "P$7") (pinfunction "P1.6_P$7") (pintype "bidirectional"))
    )
    (net (code "108") (name "unconnected-(MASTER-P2.6-PadP$15)") (class "Default")
      (node (ref "MASTER") (pin "P$15") (pinfunction "P2.6_P$15") (pintype "bidirectional"))
    )
    (net (code "109") (name "unconnected-(U$1-DB0-PadP$1)") (class "Default")
      (node (ref "U$1") (pin "P$1") (pinfunction "DB0_P$1") (pintype "bidirectional"))
    )
    (net (code "110") (name "unconnected-(U$1-DB1-PadP$2)") (class "Default")
      (node (ref "U$1") (pin "P$2") (pinfunction "DB1_P$2") (pintype "bidirectional"))
    )
    (net (code "111") (name "unconnected-(U$1-DB2-PadP$3)") (class "Default")
      (node (ref "U$1") (pin "P$3") (pinfunction "DB2_P$3") (pintype "bidirectional"))
    )
    (net (code "112") (name "unconnected-(U$1-DB3-PadP$4)") (class "Default")
      (node (ref "U$1") (pin "P$4") (pinfunction "DB3_P$4") (pintype "bidirectional"))
    )
    (net (code "113") (name "unconnected-(U$1-LED+-PadP$12)") (class "Default")
      (node (ref "U$1") (pin "P$12") (pinfunction "LED+_P$12") (pintype "bidirectional"))
    )
    (net (code "114") (name "unconnected-(U$1-LED--PadP$13)") (class "Default")
      (node (ref "U$1") (pin "P$13") (pinfunction "LED-_P$13") (pintype "bidirectional"))
    )
  )
)
